# RAMPSdisplay.net
KiCad netlist of a schematic drawn in EAGLE
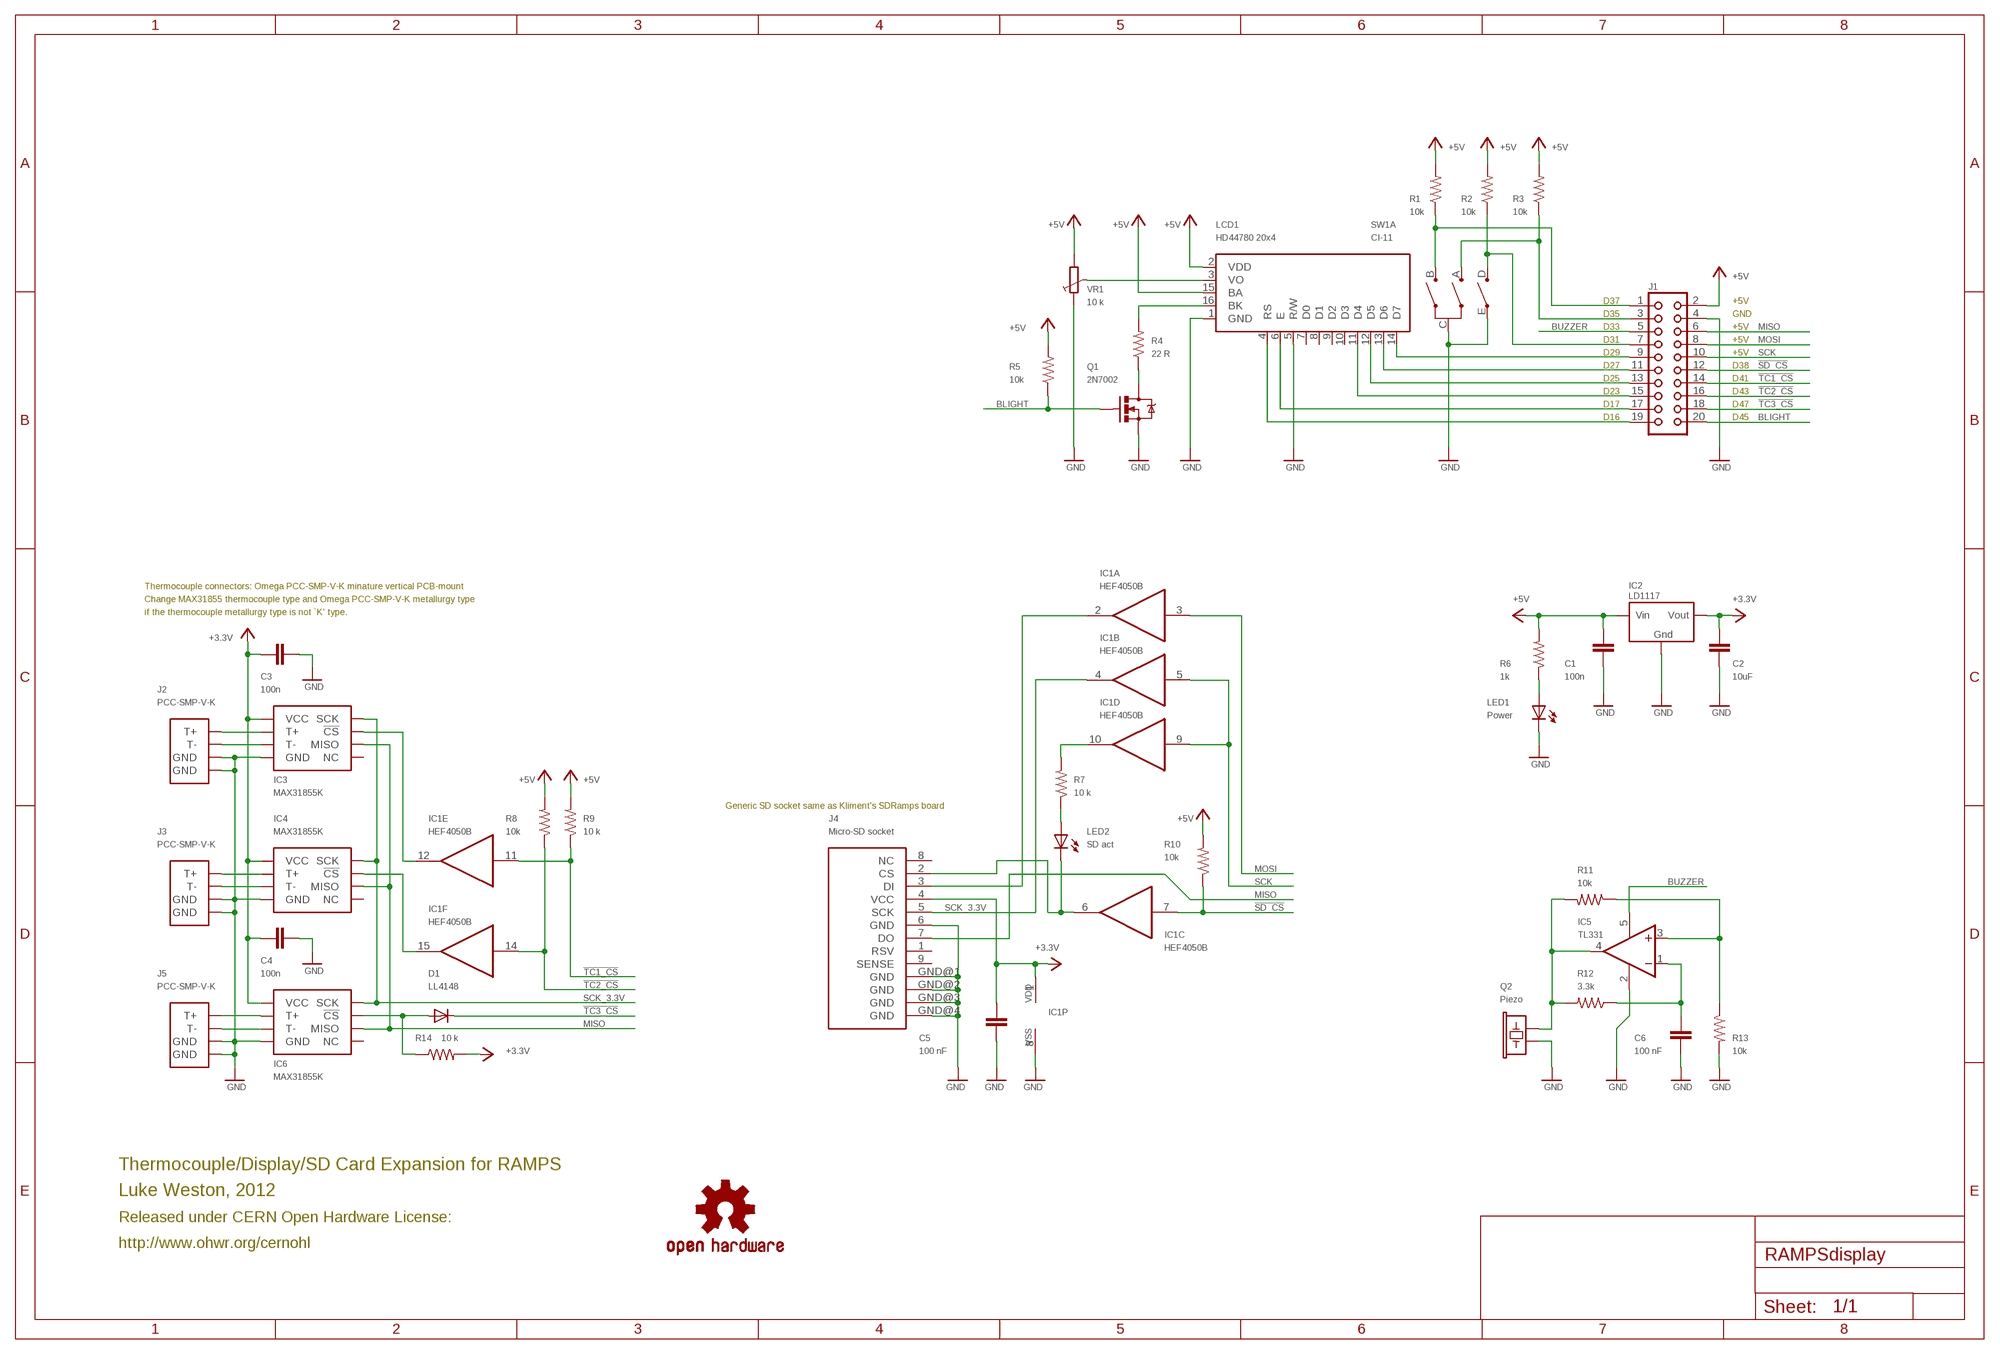
[diagram p0: schematic, sheet 1]

(export (version "E")
  (design (tool "Eeschema 10.0.6"))
  (components
    (comp (ref "C1")
      (value "100n")
      (footprint "eagle-import:C0805K")
      (libsource (lib "eagle-import") (part "C-EUC0805K"))
    )
    (comp (ref "C2")
      (value "10uF")
      (footprint "eagle-import:C0805K")
      (libsource (lib "eagle-import") (part "C-EUC0805K"))
    )
    (comp (ref "C3")
      (value "100n")
      (footprint "eagle-import:C0805K")
      (libsource (lib "eagle-import") (part "C-EUC0805K"))
    )
    (comp (ref "C4")
      (value "100n")
      (footprint "eagle-import:C0805K")
      (libsource (lib "eagle-import") (part "C-EUC0805K"))
    )
    (comp (ref "C5")
      (value "100 nF")
      (footprint "eagle-import:C0805K")
      (libsource (lib "eagle-import") (part "C-EUC0805K"))
    )
    (comp (ref "C6")
      (value "100 nF")
      (footprint "eagle-import:C0805K")
      (libsource (lib "eagle-import") (part "C-EUC0805K"))
    )
    (comp (ref "D1")
      (value "LL4148")
      (footprint "eagle-import:SOD80C")
      (libsource (lib "eagle-import") (part "DIODE-SOD80C"))
    )
    (comp (ref "IC1")
      (value "HEF4050B")
      (footprint "eagle-import:SO16")
      (libsource (lib "eagle-import") (part "4050D"))
    )
    (comp (ref "IC2")
      (value "LD1117")
      (footprint "eagle-import:SOT223")
      (fields (field (name "MPN") "REG1117"))
      (libsource (lib "eagle-import") (part "REG1117"))
    )
    (comp (ref "IC3")
      (value "MAX31855K")
      (footprint "eagle-import:MCLENG_SOIC-8")
      (libsource (lib "eagle-import") (part "MCLENG_MAX6675MAX31855"))
    )
    (comp (ref "IC4")
      (value "MAX31855K")
      (footprint "eagle-import:MCLENG_SOIC-8")
      (libsource (lib "eagle-import") (part "MCLENG_MAX6675MAX31855"))
    )
    (comp (ref "IC5")
      (value "TL331")
      (footprint "eagle-import:DBV-R-PDSO-G5")
      (libsource (lib "eagle-import") (part "TL331"))
    )
    (comp (ref "IC6")
      (value "MAX31855K")
      (footprint "eagle-import:MCLENG_SOIC-8")
      (libsource (lib "eagle-import") (part "MCLENG_MAX6675MAX31855"))
    )
    (comp (ref "J1")
      (value "CON20")
      (footprint "eagle-import:CON20")
      (libsource (lib "eagle-import") (part "CON20"))
    )
    (comp (ref "J2")
      (value "PCC-SMP-V-K")
      (footprint "eagle-import:MCLAUGHLINENG_TC_JACK")
      (libsource (lib "eagle-import") (part "MCLAUGHLINENG_TC_JACK"))
    )
    (comp (ref "J3")
      (value "PCC-SMP-V-K")
      (footprint "eagle-import:MCLAUGHLINENG_TC_JACK")
      (libsource (lib "eagle-import") (part "MCLAUGHLINENG_TC_JACK"))
    )
    (comp (ref "J4")
      (value "Micro-SD socket")
      (footprint "eagle-import:MICROSD_PP")
      (libsource (lib "eagle-import") (part "MICROSD_PP"))
    )
    (comp (ref "J5")
      (value "PCC-SMP-V-K")
      (footprint "eagle-import:MCLAUGHLINENG_TC_JACK")
      (libsource (lib "eagle-import") (part "MCLAUGHLINENG_TC_JACK"))
    )
    (comp (ref "LCD1")
      (value "HD44780 20x4")
      (footprint "eagle-import:HDM20416L")
      (libsource (lib "eagle-import") (part "HDM20416L"))
    )
    (comp (ref "LED1")
      (value "Power")
      (footprint "eagle-import:CHIPLED_0805")
      (libsource (lib "eagle-import") (part "LEDCHIPLED_0805"))
    )
    (comp (ref "LED2")
      (value "SD act")
      (footprint "eagle-import:CHIPLED_0805")
      (libsource (lib "eagle-import") (part "LEDCHIPLED_0805"))
    )
    (comp (ref "Q1")
      (value "2N7002")
      (footprint "eagle-import:SOT23-3")
      (libsource (lib "eagle-import") (part "MOSFET-NCHANNELSMD"))
    )
    (comp (ref "Q2")
      (value "Piezo")
      (footprint "eagle-import:FREETRONICS-MASTER-V1_BUZZER-12X12-SMT")
      (libsource (lib "eagle-import") (part "FREETRONICS-MASTER-V1_BUZZERSMD12X12"))
    )
    (comp (ref "R1")
      (value "10k")
      (footprint "eagle-import:M0805")
      (libsource (lib "eagle-import") (part "R-US_M0805"))
    )
    (comp (ref "R2")
      (value "10k")
      (footprint "eagle-import:M0805")
      (libsource (lib "eagle-import") (part "R-US_M0805"))
    )
    (comp (ref "R3")
      (value "10k")
      (footprint "eagle-import:M0805")
      (libsource (lib "eagle-import") (part "R-US_M0805"))
    )
    (comp (ref "R4")
      (value "22 R")
      (footprint "eagle-import:M0805")
      (libsource (lib "eagle-import") (part "R-US_M0805"))
    )
    (comp (ref "R5")
      (value "10k")
      (footprint "eagle-import:M0805")
      (libsource (lib "eagle-import") (part "R-US_M0805"))
    )
    (comp (ref "R6")
      (value "1k")
      (footprint "eagle-import:M0805")
      (libsource (lib "eagle-import") (part "R-US_M0805"))
    )
    (comp (ref "R7")
      (value "10 k")
      (footprint "eagle-import:M0805")
      (libsource (lib "eagle-import") (part "R-US_M0805"))
    )
    (comp (ref "R8")
      (value "10k")
      (footprint "eagle-import:M0805")
      (libsource (lib "eagle-import") (part "R-US_M0805"))
    )
    (comp (ref "R9")
      (value "10 k")
      (footprint "eagle-import:M0805")
      (libsource (lib "eagle-import") (part "R-US_M0805"))
    )
    (comp (ref "R10")
      (value "10k")
      (footprint "eagle-import:M0805")
      (libsource (lib "eagle-import") (part "R-US_M0805"))
    )
    (comp (ref "R11")
      (value "10k")
      (footprint "eagle-import:M0805")
      (libsource (lib "eagle-import") (part "R-US_M0805"))
    )
    (comp (ref "R12")
      (value "3.3k")
      (footprint "eagle-import:M0805")
      (libsource (lib "eagle-import") (part "R-US_M0805"))
    )
    (comp (ref "R13")
      (value "10k")
      (footprint "eagle-import:M0805")
      (libsource (lib "eagle-import") (part "R-US_M0805"))
    )
    (comp (ref "R14")
      (value "10 k")
      (footprint "eagle-import:M0805")
      (libsource (lib "eagle-import") (part "R-US_M0805"))
    )
    (comp (ref "SW1")
      (value "CI-11")
      (footprint "eagle-import:CI-11")
      (libsource (lib "eagle-import") (part "CI-11"))
    )
    (comp (ref "U$")
      (value "OSHW-LOGOS")
      (footprint "eagle-import:OSHW-LOGO-S")
      (libsource (lib "eagle-import") (part "OSHW-LOGOS"))
    )
    (comp (ref "VR1")
      (value "10 k")
      (footprint "eagle-import:CT6")
      (libsource (lib "eagle-import") (part "TRIM_EU-CT6"))
    )
  )
  (nets
    (net (code "1") (name "+3.3V") (class "Default")
      (node (ref "C2") (pin "1") (pinfunction "1_1") (pintype "passive"))
      (node (ref "C3") (pin "1") (pinfunction "1_1") (pintype "passive"))
      (node (ref "C4") (pin "1") (pinfunction "1_1") (pintype "passive"))
      (node (ref "C5") (pin "1") (pinfunction "1_1") (pintype "passive"))
      (node (ref "IC1") (pin "1") (pinfunction "VDD_1") (pintype "power_in"))
      (node (ref "IC2") (pin "2") (pinfunction "VOUT_2") (pintype "output"))
      (node (ref "IC3") (pin "VCC") (pinfunction "VCC_VCC") (pintype "bidirectional"))
      (node (ref "IC4") (pin "VCC") (pinfunction "VCC_VCC") (pintype "bidirectional"))
      (node (ref "IC6") (pin "VCC") (pinfunction "VCC_VCC") (pintype "bidirectional"))
      (node (ref "J4") (pin "4") (pinfunction "VCC_4") (pintype "bidirectional"))
      (node (ref "R14") (pin "2") (pinfunction "2_2") (pintype "passive"))
    )
    (net (code "2") (name "+5V") (class "Default")
      (node (ref "C1") (pin "1") (pinfunction "1_1") (pintype "passive"))
      (node (ref "IC2") (pin "3") (pinfunction "VIN_3") (pintype "input"))
      (node (ref "J1") (pin "2") (pinfunction "2_2") (pintype "passive"))
      (node (ref "LCD1") (pin "15") (pinfunction "BA_15") (pintype "bidirectional"))
      (node (ref "LCD1") (pin "2") (pinfunction "VDD_2") (pintype "bidirectional"))
      (node (ref "R1") (pin "2") (pinfunction "2_2") (pintype "passive"))
      (node (ref "R10") (pin "2") (pinfunction "2_2") (pintype "passive"))
      (node (ref "R2") (pin "2") (pinfunction "2_2") (pintype "passive"))
      (node (ref "R3") (pin "2") (pinfunction "2_2") (pintype "passive"))
      (node (ref "R5") (pin "2") (pinfunction "2_2") (pintype "passive"))
      (node (ref "R6") (pin "2") (pinfunction "2_2") (pintype "passive"))
      (node (ref "R8") (pin "2") (pinfunction "2_2") (pintype "passive"))
      (node (ref "R9") (pin "2") (pinfunction "2_2") (pintype "passive"))
      (node (ref "VR1") (pin "A") (pinfunction "A_A") (pintype "passive"))
    )
    (net (code "3") (name "/BLIGHT") (class "Default")
      (node (ref "J1") (pin "20") (pinfunction "20_20") (pintype "passive"))
      (node (ref "Q1") (pin "1") (pinfunction "G_1") (pintype "passive"))
      (node (ref "R5") (pin "1") (pinfunction "1_1") (pintype "passive"))
    )
    (net (code "4") (name "/BUZZER") (class "Default")
      (node (ref "IC5") (pin "5") (pinfunction "V+_5") (pintype "power_in"))
      (node (ref "J1") (pin "5") (pinfunction "5_5") (pintype "passive"))
    )
    (net (code "5") (name "/MISO") (class "Default")
      (node (ref "IC3") (pin "SO") (pinfunction "MISO_SO") (pintype "bidirectional"))
      (node (ref "IC4") (pin "SO") (pinfunction "MISO_SO") (pintype "bidirectional"))
      (node (ref "IC6") (pin "SO") (pinfunction "MISO_SO") (pintype "bidirectional"))
      (node (ref "J1") (pin "6") (pinfunction "6_6") (pintype "passive"))
      (node (ref "J4") (pin "7") (pinfunction "DO_7") (pintype "bidirectional"))
    )
    (net (code "6") (name "/MOSI") (class "Default")
      (node (ref "IC1") (pin "3") (pinfunction "I_3") (pintype "input"))
      (node (ref "J1") (pin "8") (pinfunction "8_8") (pintype "passive"))
    )
    (net (code "7") (name "/SCK") (class "Default")
      (node (ref "IC1") (pin "5") (pinfunction "I_5") (pintype "input"))
      (node (ref "IC1") (pin "9") (pinfunction "I_9") (pintype "input"))
      (node (ref "J1") (pin "10") (pinfunction "10_10") (pintype "passive"))
    )
    (net (code "8") (name "/SCK_3.3V") (class "Default")
      (node (ref "IC1") (pin "4") (pinfunction "O_4") (pintype "output"))
      (node (ref "IC3") (pin "SCK") (pinfunction "SCK_SCK") (pintype "bidirectional"))
      (node (ref "IC4") (pin "SCK") (pinfunction "SCK_SCK") (pintype "bidirectional"))
      (node (ref "IC6") (pin "SCK") (pinfunction "SCK_SCK") (pintype "bidirectional"))
      (node (ref "J4") (pin "5") (pinfunction "SCK_5") (pintype "bidirectional"))
    )
    (net (code "9") (name "/~{SD_CS}") (class "Default")
      (node (ref "IC1") (pin "7") (pinfunction "I_7") (pintype "input"))
      (node (ref "J1") (pin "12") (pinfunction "12_12") (pintype "passive"))
      (node (ref "R10") (pin "1") (pinfunction "1_1") (pintype "passive"))
    )
    (net (code "10") (name "/~{TC1_CS}") (class "Default")
      (node (ref "IC1") (pin "11") (pinfunction "I_11") (pintype "input"))
      (node (ref "J1") (pin "14") (pinfunction "14_14") (pintype "passive"))
      (node (ref "R9") (pin "1") (pinfunction "1_1") (pintype "passive"))
    )
    (net (code "11") (name "/~{TC2_CS}") (class "Default")
      (node (ref "IC1") (pin "14") (pinfunction "I_14") (pintype "input"))
      (node (ref "J1") (pin "16") (pinfunction "16_16") (pintype "passive"))
      (node (ref "R8") (pin "1") (pinfunction "1_1") (pintype "passive"))
    )
    (net (code "12") (name "/~{TC3_CS}") (class "Default")
      (node (ref "D1") (pin "C") (pinfunction "C_C") (pintype "passive"))
      (node (ref "J1") (pin "18") (pinfunction "18_18") (pintype "passive"))
    )
    (net (code "13") (name "GND") (class "Default")
      (node (ref "C1") (pin "2") (pinfunction "2_2") (pintype "passive"))
      (node (ref "C2") (pin "2") (pinfunction "2_2") (pintype "passive"))
      (node (ref "C3") (pin "2") (pinfunction "2_2") (pintype "passive"))
      (node (ref "C4") (pin "2") (pinfunction "2_2") (pintype "passive"))
      (node (ref "C5") (pin "2") (pinfunction "2_2") (pintype "passive"))
      (node (ref "C6") (pin "2") (pinfunction "2_2") (pintype "passive"))
      (node (ref "IC1") (pin "8") (pinfunction "VSS_8") (pintype "power_in"))
      (node (ref "IC2") (pin "1") (pinfunction "GND_1") (pintype "power_in"))
      (node (ref "IC3") (pin "GND") (pinfunction "GND_GND") (pintype "bidirectional"))
      (node (ref "IC4") (pin "GND") (pinfunction "GND_GND") (pintype "bidirectional"))
      (node (ref "IC5") (pin "2") (pinfunction "GND_2") (pintype "power_in"))
      (node (ref "IC6") (pin "GND") (pinfunction "GND_GND") (pintype "bidirectional"))
      (node (ref "J1") (pin "4") (pinfunction "4_4") (pintype "passive"))
      (node (ref "J2") (pin "P$1") (pinfunction "GND_P$1") (pintype "bidirectional"))
      (node (ref "J2") (pin "P$2") (pinfunction "GND_P$2") (pintype "bidirectional"))
      (node (ref "J3") (pin "P$1") (pinfunction "GND_P$1") (pintype "bidirectional"))
      (node (ref "J3") (pin "P$2") (pinfunction "GND_P$2") (pintype "bidirectional"))
      (node (ref "J4") (pin "6") (pinfunction "GND_6") (pintype "bidirectional"))
      (node (ref "J4") (pin "GND@1") (pinfunction "GND_GND@1") (pintype "bidirectional"))
      (node (ref "J4") (pin "GND@2") (pinfunction "GND_GND@2") (pintype "bidirectional"))
      (node (ref "J4") (pin "GND@3") (pinfunction "GND_GND@3") (pintype "bidirectional"))
      (node (ref "J4") (pin "GND@4") (pinfunction "GND_GND@4") (pintype "bidirectional"))
      (node (ref "J5") (pin "P$1") (pinfunction "GND_P$1") (pintype "bidirectional"))
      (node (ref "J5") (pin "P$2") (pinfunction "GND_P$2") (pintype "bidirectional"))
      (node (ref "LCD1") (pin "1") (pinfunction "GND_1") (pintype "bidirectional"))
      (node (ref "LCD1") (pin "5") (pinfunction "R/W_5") (pintype "bidirectional"))
      (node (ref "LED1") (pin "C") (pinfunction "C_C") (pintype "passive"))
      (node (ref "Q1") (pin "2") (pinfunction "S_2") (pintype "passive"))
      (node (ref "Q2") (pin "1") (pinfunction "1_1") (pintype "passive"))
      (node (ref "R13") (pin "2") (pinfunction "2_2") (pintype "passive"))
      (node (ref "SW1") (pin "C") (pinfunction "C_C") (pintype "passive"))
      (node (ref "SW1") (pin "E") (pinfunction "E_E") (pintype "passive"))
      (node (ref "VR1") (pin "E") (pinfunction "E_E") (pintype "passive"))
    )
    (net (code "14") (name "Net-(IC1A-O)") (class "Default")
      (node (ref "IC1") (pin "2") (pinfunction "O_2") (pintype "output"))
      (node (ref "J4") (pin "3") (pinfunction "DI_3") (pintype "bidirectional"))
    )
    (net (code "15") (name "Net-(IC1C-O)") (class "Default")
      (node (ref "IC1") (pin "6") (pinfunction "O_6") (pintype "output"))
      (node (ref "J4") (pin "2") (pinfunction "CS_2") (pintype "bidirectional"))
      (node (ref "LED2") (pin "C") (pinfunction "C_C") (pintype "passive"))
    )
    (net (code "16") (name "Net-(IC1D-O)") (class "Default")
      (node (ref "IC1") (pin "10") (pinfunction "O_10") (pintype "output"))
      (node (ref "R7") (pin "2") (pinfunction "2_2") (pintype "passive"))
    )
    (net (code "17") (name "Net-(IC1E-O)") (class "Default")
      (node (ref "IC1") (pin "12") (pinfunction "O_12") (pintype "output"))
      (node (ref "IC3") (pin "CS") (pinfunction "~{CS}_CS") (pintype "bidirectional"))
    )
    (net (code "18") (name "Net-(IC1F-O)") (class "Default")
      (node (ref "IC1") (pin "15") (pinfunction "O_15") (pintype "output"))
      (node (ref "IC4") (pin "CS") (pinfunction "~{CS}_CS") (pintype "bidirectional"))
    )
    (net (code "19") (name "Net-(IC3-PadT+)") (class "Default")
      (node (ref "IC3") (pin "T+") (pinfunction "T+_T+") (pintype "bidirectional"))
      (node (ref "J2") (pin "T+") (pinfunction "T+_T+") (pintype "bidirectional"))
    )
    (net (code "20") (name "Net-(IC3-PadT-)") (class "Default")
      (node (ref "IC3") (pin "T-") (pinfunction "T-_T-") (pintype "bidirectional"))
      (node (ref "J2") (pin "T-") (pinfunction "T-_T-") (pintype "bidirectional"))
    )
    (net (code "21") (name "Net-(IC4-PadT+)") (class "Default")
      (node (ref "IC4") (pin "T+") (pinfunction "T+_T+") (pintype "bidirectional"))
      (node (ref "J3") (pin "T+") (pinfunction "T+_T+") (pintype "bidirectional"))
    )
    (net (code "22") (name "Net-(IC4-PadT-)") (class "Default")
      (node (ref "IC4") (pin "T-") (pinfunction "T-_T-") (pintype "bidirectional"))
      (node (ref "J3") (pin "T-") (pinfunction "T-_T-") (pintype "bidirectional"))
    )
    (net (code "23") (name "Net-(IC5-+IN)") (class "Default")
      (node (ref "IC5") (pin "3") (pinfunction "+IN_3") (pintype "input"))
      (node (ref "R11") (pin "1") (pinfunction "1_1") (pintype "passive"))
      (node (ref "R13") (pin "1") (pinfunction "1_1") (pintype "passive"))
    )
    (net (code "24") (name "Net-(IC5--IN)") (class "Default")
      (node (ref "C6") (pin "1") (pinfunction "1_1") (pintype "passive"))
      (node (ref "IC5") (pin "1") (pinfunction "-IN_1") (pintype "input"))
      (node (ref "R12") (pin "1") (pinfunction "1_1") (pintype "passive"))
    )
    (net (code "25") (name "Net-(IC5-OUT)") (class "Default")
      (node (ref "IC5") (pin "4") (pinfunction "OUT_4") (pintype "output"))
      (node (ref "Q2") (pin "2") (pinfunction "2_2") (pintype "passive"))
      (node (ref "R11") (pin "2") (pinfunction "2_2") (pintype "passive"))
      (node (ref "R12") (pin "2") (pinfunction "2_2") (pintype "passive"))
    )
    (net (code "26") (name "Net-(IC6-PadT+)") (class "Default")
      (node (ref "IC6") (pin "T+") (pinfunction "T+_T+") (pintype "bidirectional"))
      (node (ref "J5") (pin "T+") (pinfunction "T+_T+") (pintype "bidirectional"))
    )
    (net (code "27") (name "Net-(IC6-PadT-)") (class "Default")
      (node (ref "IC6") (pin "T-") (pinfunction "T-_T-") (pintype "bidirectional"))
      (node (ref "J5") (pin "T-") (pinfunction "T-_T-") (pintype "bidirectional"))
    )
    (net (code "28") (name "Net-(IC6-~{CS})") (class "Default")
      (node (ref "D1") (pin "A") (pinfunction "A_A") (pintype "passive"))
      (node (ref "IC6") (pin "CS") (pinfunction "~{CS}_CS") (pintype "bidirectional"))
      (node (ref "R14") (pin "1") (pinfunction "1_1") (pintype "passive"))
    )
    (net (code "29") (name "Net-(J1-Pad1)") (class "Default")
      (node (ref "J1") (pin "1") (pinfunction "1_1") (pintype "passive"))
      (node (ref "R1") (pin "1") (pinfunction "1_1") (pintype "passive"))
      (node (ref "SW1") (pin "B") (pinfunction "B_B") (pintype "passive"))
    )
    (net (code "30") (name "Net-(J1-Pad3)") (class "Default")
      (node (ref "J1") (pin "3") (pinfunction "3_3") (pintype "passive"))
      (node (ref "R3") (pin "1") (pinfunction "1_1") (pintype "passive"))
      (node (ref "SW1") (pin "A") (pinfunction "A_A") (pintype "passive"))
    )
    (net (code "31") (name "Net-(J1-Pad7)") (class "Default")
      (node (ref "J1") (pin "7") (pinfunction "7_7") (pintype "passive"))
      (node (ref "R2") (pin "1") (pinfunction "1_1") (pintype "passive"))
      (node (ref "SW1") (pin "D") (pinfunction "D_D") (pintype "passive"))
    )
    (net (code "32") (name "Net-(LCD1-BK)") (class "Default")
      (node (ref "LCD1") (pin "16") (pinfunction "BK_16") (pintype "bidirectional"))
      (node (ref "R4") (pin "2") (pinfunction "2_2") (pintype "passive"))
    )
    (net (code "33") (name "Net-(LCD1-D4)") (class "Default")
      (node (ref "J1") (pin "15") (pinfunction "15_15") (pintype "passive"))
      (node (ref "LCD1") (pin "11") (pinfunction "D4_11") (pintype "bidirectional"))
    )
    (net (code "34") (name "Net-(LCD1-D5)") (class "Default")
      (node (ref "J1") (pin "13") (pinfunction "13_13") (pintype "passive"))
      (node (ref "LCD1") (pin "12") (pinfunction "D5_12") (pintype "bidirectional"))
    )
    (net (code "35") (name "Net-(LCD1-D6)") (class "Default")
      (node (ref "J1") (pin "11") (pinfunction "11_11") (pintype "passive"))
      (node (ref "LCD1") (pin "13") (pinfunction "D6_13") (pintype "bidirectional"))
    )
    (net (code "36") (name "Net-(LCD1-D7)") (class "Default")
      (node (ref "J1") (pin "9") (pinfunction "9_9") (pintype "passive"))
      (node (ref "LCD1") (pin "14") (pinfunction "D7_14") (pintype "bidirectional"))
    )
    (net (code "37") (name "Net-(LCD1-E)") (class "Default")
      (node (ref "J1") (pin "17") (pinfunction "17_17") (pintype "passive"))
      (node (ref "LCD1") (pin "6") (pinfunction "E_6") (pintype "bidirectional"))
    )
    (net (code "38") (name "Net-(LCD1-RS)") (class "Default")
      (node (ref "J1") (pin "19") (pinfunction "19_19") (pintype "passive"))
      (node (ref "LCD1") (pin "4") (pinfunction "RS_4") (pintype "bidirectional"))
    )
    (net (code "39") (name "Net-(LCD1-VO)") (class "Default")
      (node (ref "LCD1") (pin "3") (pinfunction "VO_3") (pintype "bidirectional"))
      (node (ref "VR1") (pin "S") (pinfunction "S_S") (pintype "passive"))
    )
    (net (code "40") (name "Net-(LED1-PadA)") (class "Default")
      (node (ref "LED1") (pin "A") (pinfunction "A_A") (pintype "passive"))
      (node (ref "R6") (pin "1") (pinfunction "1_1") (pintype "passive"))
    )
    (net (code "41") (name "Net-(LED2-PadA)") (class "Default")
      (node (ref "LED2") (pin "A") (pinfunction "A_A") (pintype "passive"))
      (node (ref "R7") (pin "1") (pinfunction "1_1") (pintype "passive"))
    )
    (net (code "42") (name "Net-(Q1-D)") (class "Default")
      (node (ref "Q1") (pin "3") (pinfunction "D_3") (pintype "passive"))
      (node (ref "R4") (pin "1") (pinfunction "1_1") (pintype "passive"))
    )
    (net (code "43") (name "unconnected-(IC3-PadNC)") (class "Default")
      (node (ref "IC3") (pin "NC") (pinfunction "NC_NC") (pintype "no_connect"))
    )
    (net (code "44") (name "unconnected-(IC4-PadNC)") (class "Default")
      (node (ref "IC4") (pin "NC") (pinfunction "NC_NC") (pintype "no_connect"))
    )
    (net (code "45") (name "unconnected-(IC6-PadNC)") (class "Default")
      (node (ref "IC6") (pin "NC") (pinfunction "NC_NC") (pintype "no_connect"))
    )
    (net (code "46") (name "unconnected-(J4-NC-Pad8)") (class "Default")
      (node (ref "J4") (pin "8") (pinfunction "NC_8") (pintype "bidirectional"))
    )
    (net (code "47") (name "unconnected-(J4-RSV-Pad1)") (class "Default")
      (node (ref "J4") (pin "1") (pinfunction "RSV_1") (pintype "bidirectional"))
    )
    (net (code "48") (name "unconnected-(J4-SENSE-Pad9)") (class "Default")
      (node (ref "J4") (pin "9") (pinfunction "SENSE_9") (pintype "bidirectional"))
    )
    (net (code "49") (name "unconnected-(LCD1-D0-Pad7)") (class "Default")
      (node (ref "LCD1") (pin "7") (pinfunction "D0_7") (pintype "bidirectional"))
    )
    (net (code "50") (name "unconnected-(LCD1-D1-Pad8)") (class "Default")
      (node (ref "LCD1") (pin "8") (pinfunction "D1_8") (pintype "bidirectional"))
    )
    (net (code "51") (name "unconnected-(LCD1-D2-Pad9)") (class "Default")
      (node (ref "LCD1") (pin "9") (pinfunction "D2_9") (pintype "bidirectional"))
    )
    (net (code "52") (name "unconnected-(LCD1-D3-Pad10)") (class "Default")
      (node (ref "LCD1") (pin "10") (pinfunction "D3_10") (pintype "bidirectional"))
    )
  )
)
